# pc_heartypatch_v2_1.net
KiCad netlist of a schematic drawn in EAGLE
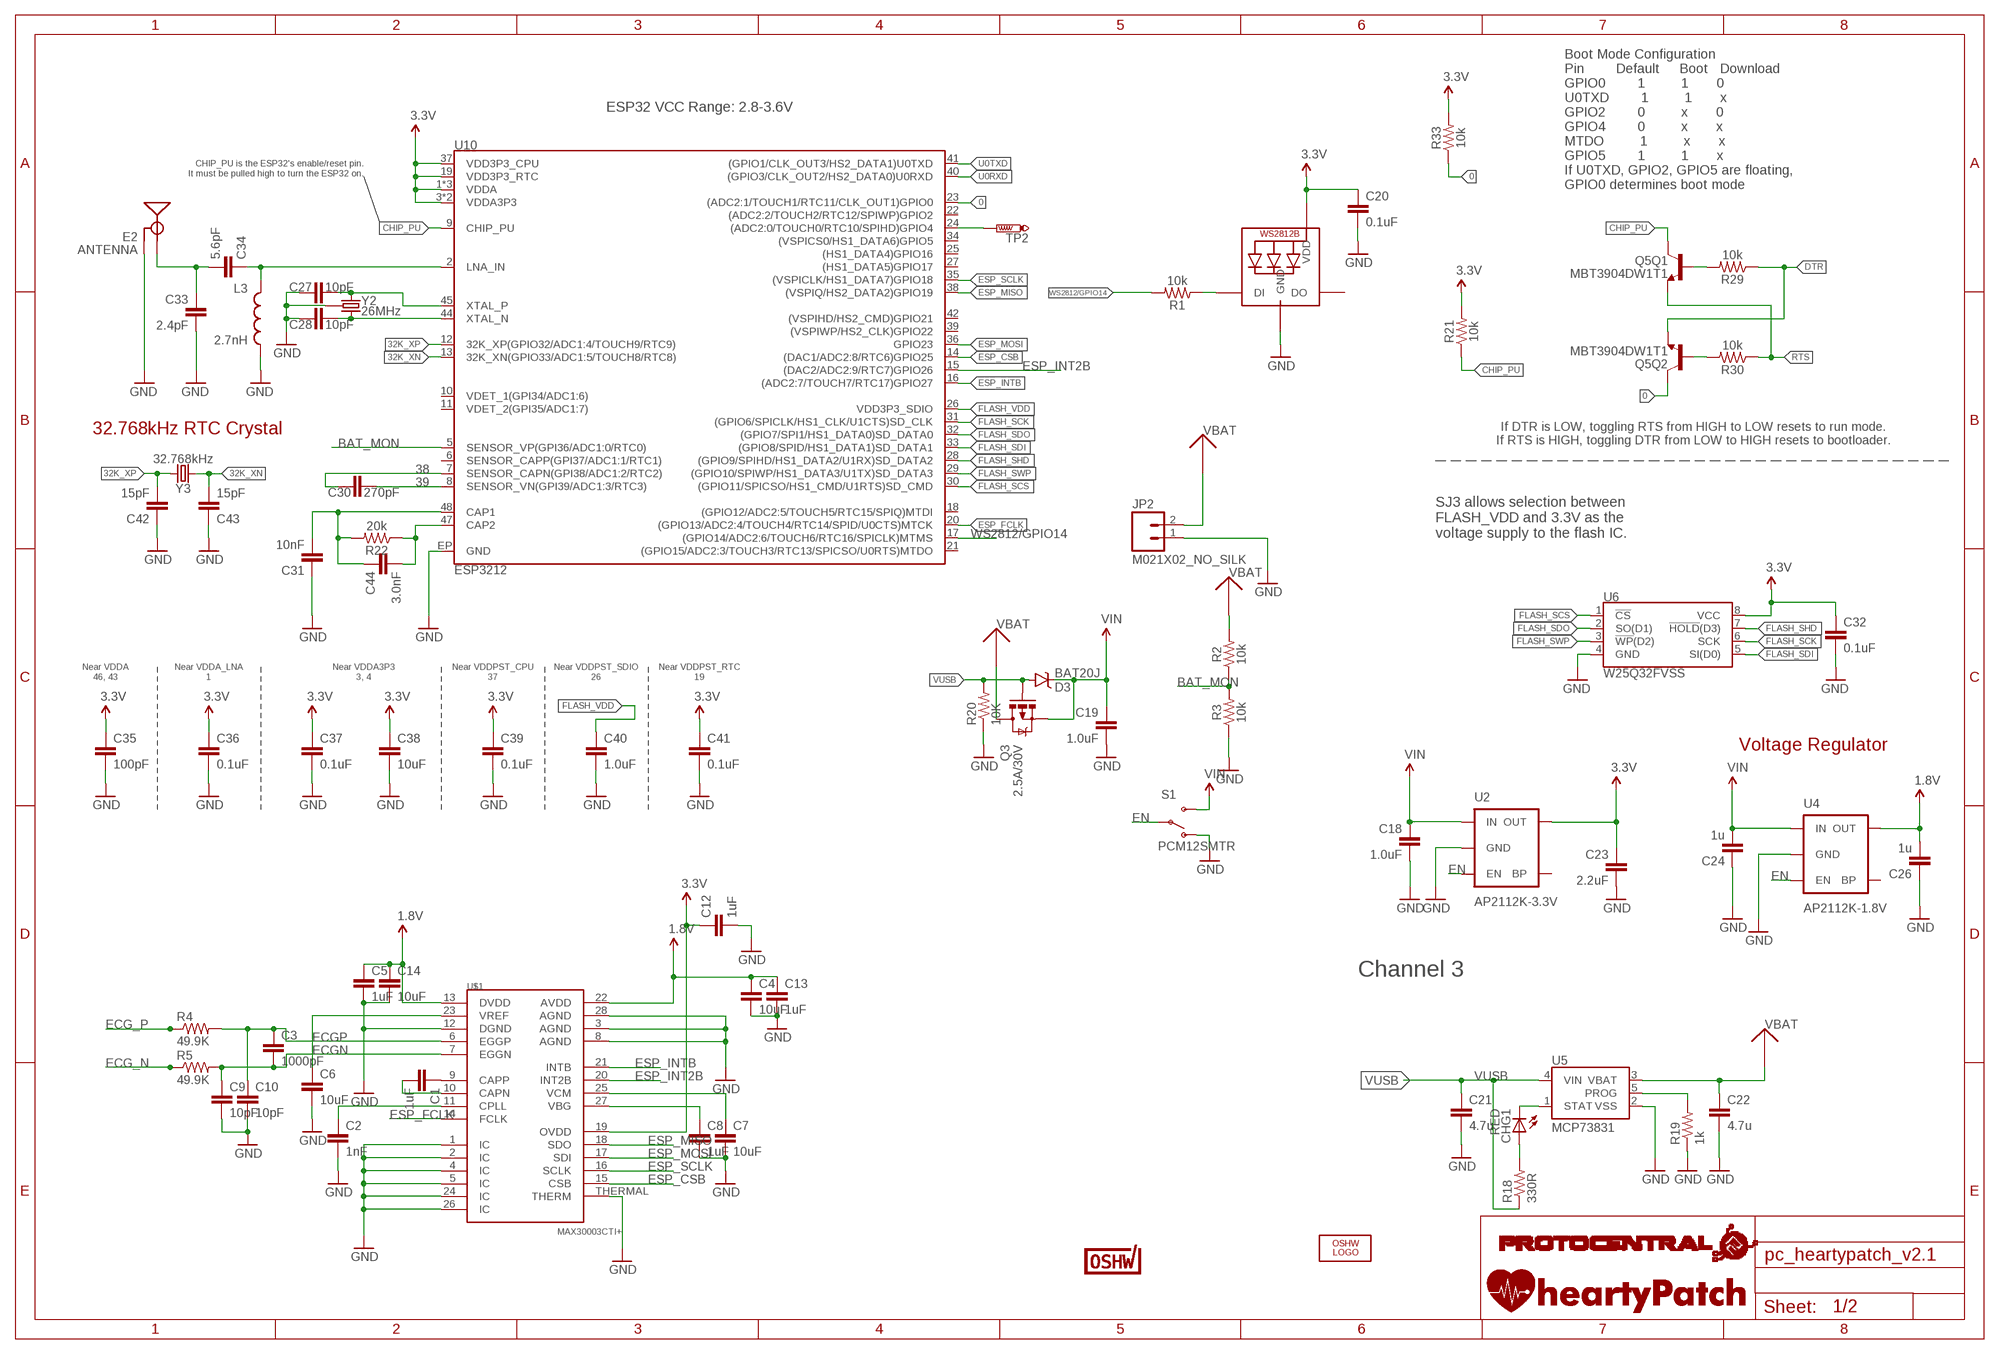
[diagram p0: schematic, sheet 1]
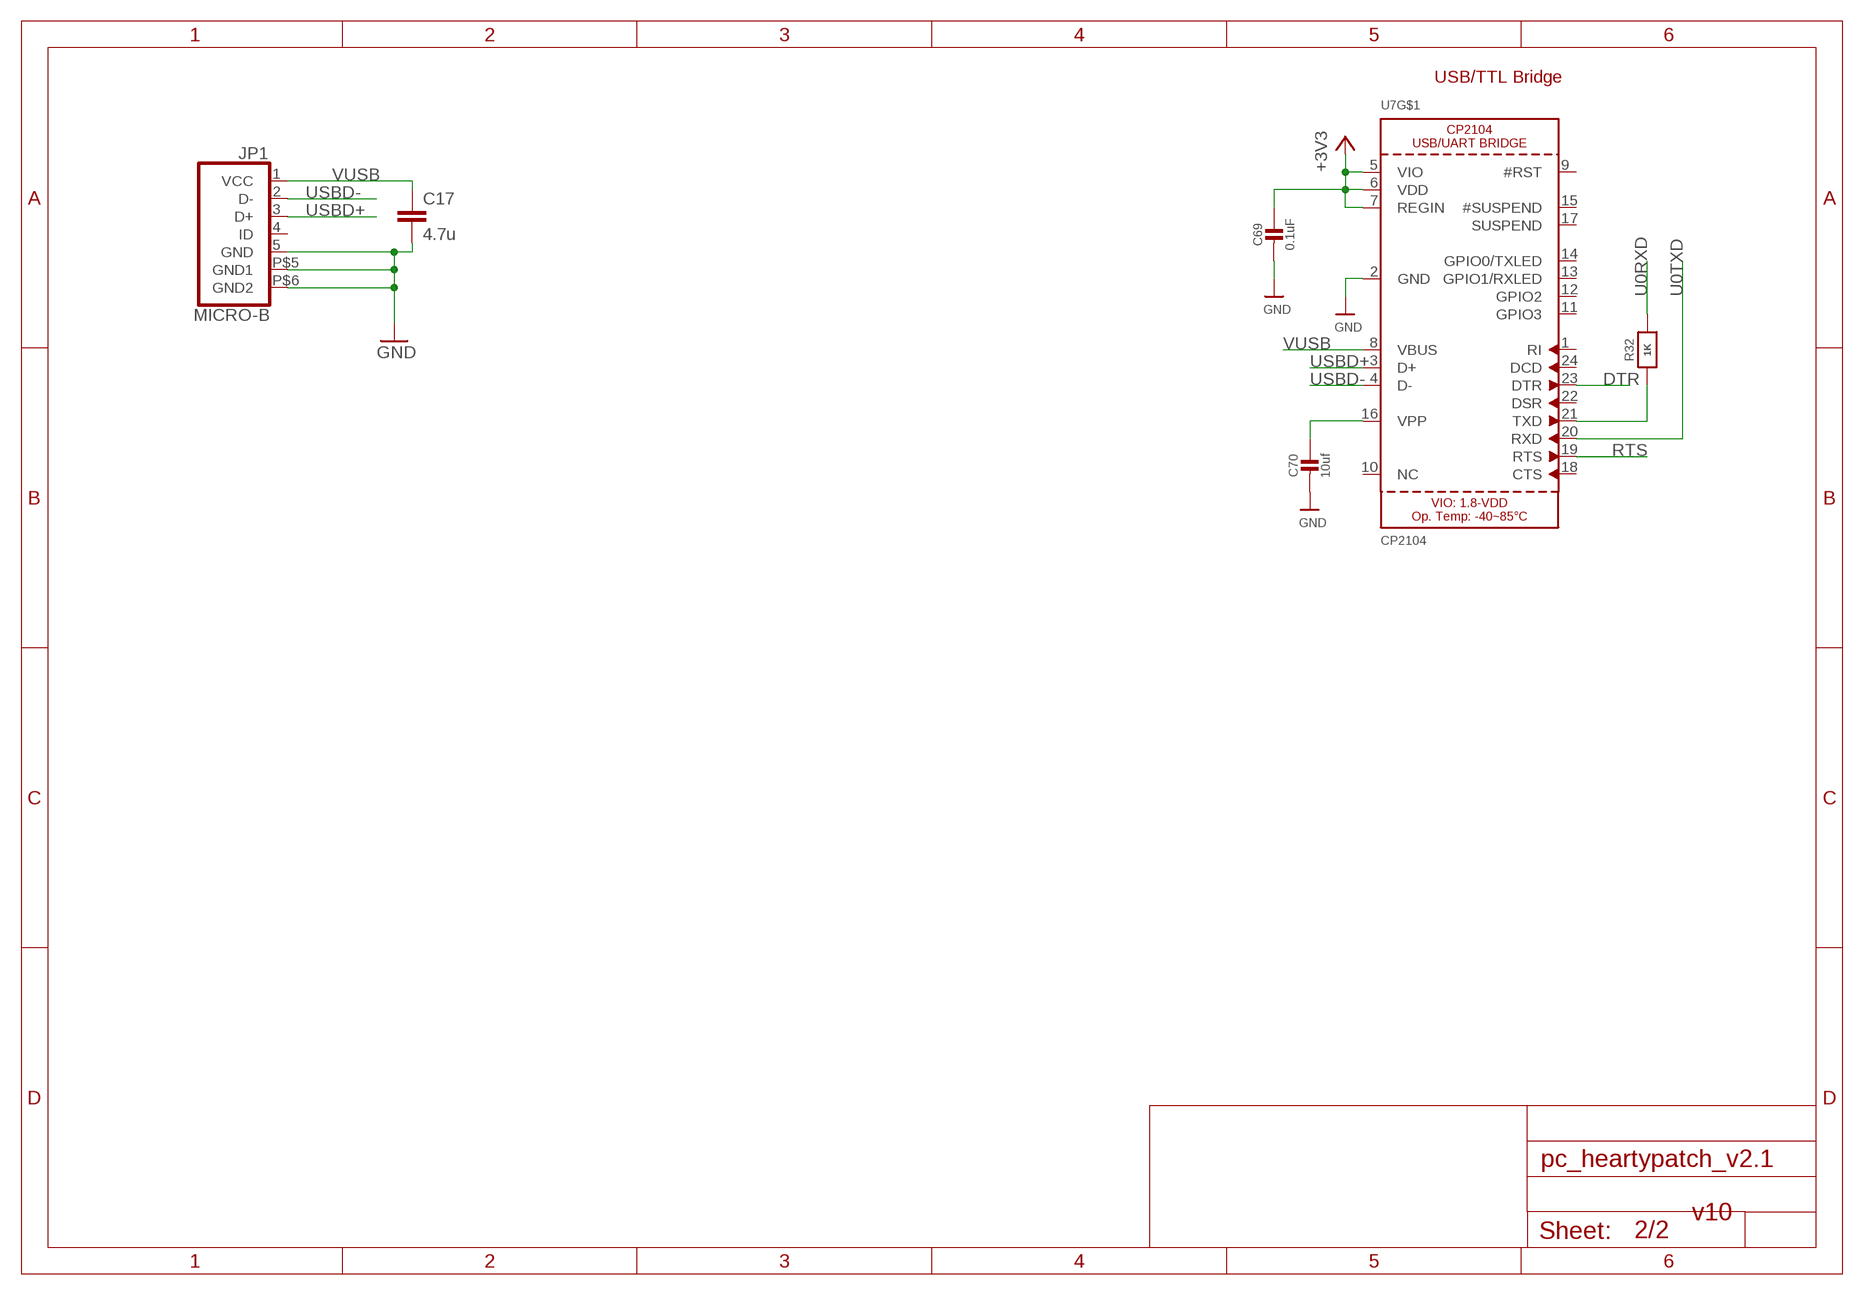
[diagram p1: schematic, sheet 2]

(export (version "E")
  (design (tool "Eeschema 10.0.6"))
  (components
    (comp (ref "C17")
      (value "4.7u")
      (footprint "eagle-import:C0805")
      (libsource (lib "eagle-import") (part "C-EUC0805"))
    )
    (comp (ref "C69")
      (value "0.1uF")
      (footprint "eagle-import:_0402")
      (libsource (lib "eagle-import") (part "CAP_CERAMIC_0402"))
    )
    (comp (ref "C70")
      (value "10uf")
      (footprint "eagle-import:0805-NO")
      (libsource (lib "eagle-import") (part "CAP_CERAMIC0805-NOOUTLINE"))
    )
    (comp (ref "JP1")
      (value "MICRO-B")
      (footprint "eagle-import:MICRO-B")
      (libsource (lib "eagle-import") (part "MICRO-B"))
    )
    (comp (ref "R32")
      (value "1K")
      (footprint "eagle-import:0603-NO")
      (libsource (lib "eagle-import") (part "RESISTOR_0603_NOOUT"))
    )
    (comp (ref "U7")
      (value "CP2104")
      (footprint "eagle-import:QFN24_4MM_SMSC")
      (libsource (lib "eagle-import") (part "CP2104"))
    )
    (comp (ref "C1")
      (value "1uF")
      (footprint "eagle-import:C0603")
      (libsource (lib "eagle-import") (part "C-EUC0603"))
    )
    (comp (ref "C2")
      (value "1nF")
      (footprint "eagle-import:C0603")
      (libsource (lib "eagle-import") (part "C-EUC0603"))
    )
    (comp (ref "C3")
      (value "1000pF")
      (footprint "eagle-import:C0402")
      (libsource (lib "eagle-import") (part "C-EUC0402"))
    )
    (comp (ref "C4")
      (value "10uF")
      (footprint "eagle-import:C0805")
      (libsource (lib "eagle-import") (part "C-EUC0805"))
    )
    (comp (ref "C5")
      (value "1uF")
      (footprint "eagle-import:C0402")
      (libsource (lib "eagle-import") (part "C-EUC0402"))
    )
    (comp (ref "C6")
      (value "10uF")
      (footprint "eagle-import:C0805")
      (libsource (lib "eagle-import") (part "C-EUC0805"))
    )
    (comp (ref "C7")
      (value "10uF")
      (footprint "eagle-import:C0805")
      (libsource (lib "eagle-import") (part "C-EUC0805"))
    )
    (comp (ref "C8")
      (value "1uF")
      (footprint "eagle-import:C0402")
      (libsource (lib "eagle-import") (part "C-EUC0402"))
    )
    (comp (ref "C9")
      (value "10pF")
      (footprint "eagle-import:C0402")
      (libsource (lib "eagle-import") (part "C-EUC0402"))
    )
    (comp (ref "C10")
      (value "10pF")
      (footprint "eagle-import:C0402")
      (libsource (lib "eagle-import") (part "C-EUC0402"))
    )
    (comp (ref "C12")
      (value "1uF")
      (footprint "eagle-import:C0402")
      (libsource (lib "eagle-import") (part "C-EUC0402"))
    )
    (comp (ref "C13")
      (value "1uF")
      (footprint "eagle-import:C0402")
      (libsource (lib "eagle-import") (part "C-EUC0402"))
    )
    (comp (ref "C14")
      (value "10uF")
      (footprint "eagle-import:C0603")
      (libsource (lib "eagle-import") (part "C-EUC0603"))
    )
    (comp (ref "C18")
      (value "1.0uF")
      (footprint "eagle-import:0805")
      (libsource (lib "eagle-import") (part "1.0UF-25V-+80/-20(0805)"))
    )
    (comp (ref "C19")
      (value "1.0uF")
      (footprint "eagle-import:C0402")
      (libsource (lib "eagle-import") (part "C-EUC0402"))
    )
    (comp (ref "C20")
      (value "0.1uF")
      (footprint "eagle-import:0603")
      (libsource (lib "eagle-import") (part "0.1UF-0603-25V-(+80/-20%)"))
    )
    (comp (ref "C21")
      (value "4.7u")
      (footprint "eagle-import:C0805")
      (libsource (lib "eagle-import") (part "C-EUC0805"))
    )
    (comp (ref "C22")
      (value "4.7u")
      (footprint "eagle-import:C0805")
      (libsource (lib "eagle-import") (part "C-EUC0805"))
    )
    (comp (ref "C23")
      (value "2.2uF")
      (footprint "eagle-import:C0805")
      (libsource (lib "eagle-import") (part "C-EUC0805"))
    )
    (comp (ref "C24")
      (value "1u")
      (footprint "eagle-import:C0805")
      (libsource (lib "eagle-import") (part "C-EUC0805"))
    )
    (comp (ref "C26")
      (value "1u")
      (footprint "eagle-import:C0805")
      (libsource (lib "eagle-import") (part "C-EUC0805"))
    )
    (comp (ref "C27")
      (value "10pF")
      (footprint "eagle-import:0603")
      (libsource (lib "eagle-import") (part "10PF-0603-50V-5%"))
    )
    (comp (ref "C28")
      (value "10pF")
      (footprint "eagle-import:0603")
      (libsource (lib "eagle-import") (part "10PF-0603-50V-5%"))
    )
    (comp (ref "C30")
      (value "270pF")
      (footprint "eagle-import:0603")
      (libsource (lib "eagle-import") (part "270PF-50V-5%(0603)"))
    )
    (comp (ref "C31")
      (value "10nF")
      (footprint "eagle-import:0603")
      (libsource (lib "eagle-import") (part "10NF-0603-50V-10%"))
    )
    (comp (ref "C32")
      (value "0.1uF")
      (footprint "eagle-import:0402")
      (libsource (lib "eagle-import") (part "0.1UF-0402-16V-10%"))
    )
    (comp (ref "C33")
      (value "2.4pF")
      (footprint "eagle-import:0603")
      (libsource (lib "eagle-import") (part "2.4PF-0603-50V-5%"))
    )
    (comp (ref "C34")
      (value "5.6pF")
      (footprint "eagle-import:0603")
      (libsource (lib "eagle-import") (part "5.6PF-50V-5%(0603)"))
    )
    (comp (ref "C35")
      (value "100pF")
      (footprint "eagle-import:0603")
      (libsource (lib "eagle-import") (part "100PF-0603-50V-5%"))
    )
    (comp (ref "C36")
      (value "0.1uF")
      (footprint "eagle-import:0603")
      (libsource (lib "eagle-import") (part "0.1UF-0603-25V-(+80/-20%)"))
    )
    (comp (ref "C37")
      (value "0.1uF")
      (footprint "eagle-import:0603")
      (libsource (lib "eagle-import") (part "0.1UF-0603-25V-(+80/-20%)"))
    )
    (comp (ref "C38")
      (value "10uF")
      (footprint "eagle-import:0603")
      (libsource (lib "eagle-import") (part "10UF-0603-6.3V-20%"))
    )
    (comp (ref "C39")
      (value "0.1uF")
      (footprint "eagle-import:0402")
      (libsource (lib "eagle-import") (part "0.1UF-0402-16V-10%"))
    )
    (comp (ref "C40")
      (value "1.0uF")
      (footprint "eagle-import:0603")
      (libsource (lib "eagle-import") (part "1.0UF-0603-16V-10%"))
    )
    (comp (ref "C41")
      (value "0.1uF")
      (footprint "eagle-import:0603")
      (libsource (lib "eagle-import") (part "0.1UF-0603-25V-(+80/-20%)"))
    )
    (comp (ref "C42")
      (value "15pF")
      (footprint "eagle-import:0603")
      (libsource (lib "eagle-import") (part "15PF-0603-50V-5%"))
    )
    (comp (ref "C43")
      (value "15pF")
      (footprint "eagle-import:0603")
      (libsource (lib "eagle-import") (part "15PF-0603-50V-5%"))
    )
    (comp (ref "C44")
      (value "3.0nF")
      (footprint "eagle-import:0603")
      (libsource (lib "eagle-import") (part "3.0NF-0603-50V-5%"))
    )
    (comp (ref "CHG1")
      (value "RED")
      (footprint "eagle-import:CHIPLED_0603")
      (libsource (lib "eagle-import") (part "LEDCHIPLED_0603"))
    )
    (comp (ref "D3")
      (value "BAT20J")
      (footprint "eagle-import:SOD-323")
      (libsource (lib "eagle-import") (part "DIODE-SCHOTTKY-BAT20J"))
    )
    (comp (ref "E2")
      (value "ANTENNA")
      (footprint "eagle-import:TRACE_ANTENNA_2.4GHZ_25.7MM_TUNED")
      (libsource (lib "eagle-import") (part "ANTENNATRACE-TUNED"))
    )
    (comp (ref "JP2")
      (value "M021X02_NO_SILK")
      (footprint "eagle-import:1X02_NO_SILK")
      (libsource (lib "eagle-import") (part "M021X02_NO_SILK"))
    )
    (comp (ref "L3")
      (value "2.7nH")
      (footprint "eagle-import:0603")
      (libsource (lib "eagle-import") (part "INDUCTOR0603"))
    )
    (comp (ref "LED1")
      (value "WS2812B5050")
      (footprint "eagle-import:WS2812B")
      (libsource (lib "eagle-import") (part "WS2812B5050"))
    )
    (comp (ref "LOGO1")
      (value "OSHW_LOGO_FILLX0200-NT")
      (footprint "eagle-import:OSHW_FILLX200_NOTEXT")
      (libsource (lib "eagle-import") (part "OSHW_LOGO_FILLX0200-NT"))
    )
    (comp (ref "Q3")
      (value "2.5A/30V")
      (footprint "eagle-import:SOT23-3")
      (libsource (lib "eagle-import") (part "MOSFET-PCHANNELDMG2307L"))
    )
    (comp (ref "Q5")
      (value "MBT3904DW1T1")
      (footprint "eagle-import:SC70-6")
      (libsource (lib "eagle-import") (part "MBT3904DW1T1"))
    )
    (comp (ref "R1")
      (value "10k")
      (footprint "eagle-import:0603")
      (libsource (lib "eagle-import") (part "10KOHM-1/10W-1%(0603)0603"))
    )
    (comp (ref "R2")
      (value "10k")
      (footprint "eagle-import:0603")
      (libsource (lib "eagle-import") (part "10KOHM-1/10W-1%(0603)0603"))
    )
    (comp (ref "R3")
      (value "10k")
      (footprint "eagle-import:0603")
      (libsource (lib "eagle-import") (part "10KOHM-1/10W-1%(0603)0603"))
    )
    (comp (ref "R4")
      (value "49.9K")
      (footprint "eagle-import:0805")
      (libsource (lib "eagle-import") (part "RESISTOR0805-RES"))
    )
    (comp (ref "R5")
      (value "49.9K")
      (footprint "eagle-import:0805")
      (libsource (lib "eagle-import") (part "RESISTOR0805-RES"))
    )
    (comp (ref "R18")
      (value "330R")
      (footprint "eagle-import:R0402")
      (libsource (lib "eagle-import") (part "R-US_R0402"))
    )
    (comp (ref "R19")
      (value "1k")
      (footprint "eagle-import:R0402")
      (libsource (lib "eagle-import") (part "R-US_R0402"))
    )
    (comp (ref "R20")
      (value "10K")
      (footprint "eagle-import:R0402")
      (libsource (lib "eagle-import") (part "R-US_R0402"))
    )
    (comp (ref "R21")
      (value "10k")
      (footprint "eagle-import:0603")
      (libsource (lib "eagle-import") (part "10KOHM-1/10W-1%(0603)0603"))
    )
    (comp (ref "R22")
      (value "20k")
      (footprint "eagle-import:0603")
      (libsource (lib "eagle-import") (part "20KOHM-0603-1/10W-1%"))
    )
    (comp (ref "R29")
      (value "10k")
      (footprint "eagle-import:0603")
      (libsource (lib "eagle-import") (part "10KOHM-0603-1/10W-1%"))
    )
    (comp (ref "R30")
      (value "10k")
      (footprint "eagle-import:0603")
      (libsource (lib "eagle-import") (part "10KOHM-0603-1/10W-1%"))
    )
    (comp (ref "R33")
      (value "10k")
      (footprint "eagle-import:0603")
      (libsource (lib "eagle-import") (part "10KOHM-1/10W-1%(0603)0603"))
    )
    (comp (ref "S1")
      (value "PCM12SMTR")
      (footprint "eagle-import:SWITCH-SPST-SMD-A")
      (libsource (lib "eagle-import") (part "SWITCH-SPDT-SMD-A"))
    )
    (comp (ref "TP2")
      (value "PTR1TP10SQ")
      (footprint "eagle-import:TP10SQ")
      (libsource (lib "eagle-import") (part "PTR1TP10SQ"))
    )
    (comp (ref "U$1")
      (value "MAX30003CTI+")
      (footprint "eagle-import:QFN-28")
      (libsource (lib "eagle-import") (part "MAX30003"))
    )
    (comp (ref "U$8")
      (value "HEARTYPATCHHEART")
      (footprint "eagle-import:HEARTYPATCH")
      (libsource (lib "eagle-import") (part "HEARTYPATCHHEART"))
    )
    (comp (ref "U$9")
      (value "PROTY_LOGO_WITH_TEXT")
      (footprint "eagle-import:PROTY_WITH_TEXT")
      (libsource (lib "eagle-import") (part "PROTY_LOGO_WITH_TEXT"))
    )
    (comp (ref "U$10")
      (value "CERT-SMALL")
      (footprint "eagle-import:CERT-SMALL-SILK")
      (libsource (lib "eagle-import") (part "CERT-SMALL"))
    )
    (comp (ref "U2")
      (value "AP2112K-3.3V")
      (footprint "eagle-import:SOT23-5")
      (libsource (lib "eagle-import") (part "V_REG_LDOSMD"))
    )
    (comp (ref "U4")
      (value "AP2112K-1.8V")
      (footprint "eagle-import:SOT23-5")
      (libsource (lib "eagle-import") (part "V_REG_LDOSMD"))
    )
    (comp (ref "U5")
      (value "MCP73831")
      (footprint "eagle-import:SOT23-5")
      (libsource (lib "eagle-import") (part "MCP73831"))
    )
    (comp (ref "U6")
      (value "W25Q32FVSS")
      (footprint "eagle-import:SOIC-8")
      (libsource (lib "eagle-import") (part "W25Q32FVSS"))
    )
    (comp (ref "U10")
      (value "ESP3212")
      (footprint "eagle-import:QFN48-0.4MM")
      (libsource (lib "eagle-import") (part "ESP3212"))
    )
    (comp (ref "Y2")
      (value "26MHz")
      (footprint "eagle-import:CRYSTAL-SMD-3.2X2.5")
      (libsource (lib "eagle-import") (part "CRYSTAL-GROUNDED3.2X2.5"))
    )
    (comp (ref "Y3")
      (value "32.768kHz")
      (footprint "eagle-import:CRYSTAL-SMD-3.2X1.5MM")
      (libsource (lib "eagle-import") (part "CRYSTAL-32.768KHZSMD-3.2X1.5"))
    )
  )
  (nets
    (net (code "1") (name "+3V3") (class "Default")
      (node (ref "C69") (pin "1") (pinfunction "1_1") (pintype "passive"))
      (node (ref "U7") (pin "5") (pinfunction "VIO_5") (pintype "power_in"))
      (node (ref "U7") (pin "6") (pinfunction "VDD_6") (pintype "power_in"))
      (node (ref "U7") (pin "7") (pinfunction "REGIN_7") (pintype "power_in"))
    )
    (net (code "2") (name "0") (class "Default")
      (node (ref "Q5") (pin "6") (pinfunction "C_6") (pintype "passive"))
      (node (ref "R33") (pin "1") (pinfunction "1_1") (pintype "passive"))
      (node (ref "U10") (pin "23") (pinfunction "(ADC2:1/TOUCH1/RTC11/CLK_OUT1)GPIO0_23") (pintype "bidirectional"))
    )
    (net (code "3") (name "1.8V") (class "Default")
      (node (ref "C13") (pin "1") (pinfunction "1_1") (pintype "passive"))
      (node (ref "C14") (pin "1") (pinfunction "1_1") (pintype "passive"))
      (node (ref "C26") (pin "2") (pinfunction "2_2") (pintype "passive"))
      (node (ref "C4") (pin "1") (pinfunction "1_1") (pintype "passive"))
      (node (ref "C5") (pin "1") (pinfunction "1_1") (pintype "passive"))
      (node (ref "U$1") (pin "13") (pinfunction "DVDD_13") (pintype "bidirectional"))
      (node (ref "U$1") (pin "22") (pinfunction "AVDD_22") (pintype "bidirectional"))
      (node (ref "U4") (pin "5") (pinfunction "OUT_5") (pintype "passive"))
    )
    (net (code "4") (name "3.3V") (class "Default")
      (node (ref "C12") (pin "1") (pinfunction "1_1") (pintype "passive"))
      (node (ref "C20") (pin "1") (pinfunction "1_1") (pintype "passive"))
      (node (ref "C23") (pin "1") (pinfunction "1_1") (pintype "passive"))
      (node (ref "C32") (pin "1") (pinfunction "1_1") (pintype "passive"))
      (node (ref "C35") (pin "1") (pinfunction "1_1") (pintype "passive"))
      (node (ref "C36") (pin "1") (pinfunction "1_1") (pintype "passive"))
      (node (ref "C37") (pin "1") (pinfunction "1_1") (pintype "passive"))
      (node (ref "C38") (pin "1") (pinfunction "1_1") (pintype "passive"))
      (node (ref "C39") (pin "1") (pinfunction "1_1") (pintype "passive"))
      (node (ref "C41") (pin "1") (pinfunction "1_1") (pintype "passive"))
      (node (ref "LED1") (pin "1-VDD") (pinfunction "VDD_1-VDD") (pintype "power_in"))
      (node (ref "R21") (pin "2") (pinfunction "2_2") (pintype "passive"))
      (node (ref "R33") (pin "2") (pinfunction "2_2") (pintype "passive"))
      (node (ref "U$1") (pin "19") (pinfunction "OVDD_19") (pintype "bidirectional"))
      (node (ref "U10") (pin "1") (pinfunction "VDDA_1") (pintype "bidirectional"))
      (node (ref "U10") (pin "19") (pinfunction "VDD3P3_RTC_19") (pintype "bidirectional"))
      (node (ref "U10") (pin "3") (pinfunction "VDDA3P3_3") (pintype "bidirectional"))
      (node (ref "U10") (pin "37") (pinfunction "VDD3P3_CPU_37") (pintype "bidirectional"))
      (node (ref "U10") (pin "4") (pinfunction "VDDA3P3_4") (pintype "bidirectional"))
      (node (ref "U10") (pin "43") (pinfunction "VDDA_43") (pintype "bidirectional"))
      (node (ref "U10") (pin "46") (pinfunction "VDDA_46") (pintype "bidirectional"))
      (node (ref "U2") (pin "5") (pinfunction "OUT_5") (pintype "passive"))
      (node (ref "U6") (pin "8") (pinfunction "VCC_8") (pintype "bidirectional"))
    )
    (net (code "5") (name "32K_XN") (class "Default")
      (node (ref "C43") (pin "2") (pinfunction "2_2") (pintype "passive"))
      (node (ref "U10") (pin "13") (pinfunction "32K_XN(GPIO33/ADC1:5/TOUCH8/RTC8)_13") (pintype "bidirectional"))
      (node (ref "Y3") (pin "P$2") (pinfunction "2_P$2") (pintype "passive"))
    )
    (net (code "6") (name "32K_XP") (class "Default")
      (node (ref "C42") (pin "2") (pinfunction "2_2") (pintype "passive"))
      (node (ref "U10") (pin "12") (pinfunction "32K_XP(GPIO32/ADC1:4/TOUCH9/RTC9)_12") (pintype "bidirectional"))
      (node (ref "Y3") (pin "P$1") (pinfunction "1_P$1") (pintype "passive"))
    )
    (net (code "7") (name "38") (class "Default")
      (node (ref "C30") (pin "1") (pinfunction "1_1") (pintype "passive"))
      (node (ref "U10") (pin "7") (pinfunction "SENSOR_CAPN(GPI38/ADC1:2/RTC2)_7") (pintype "bidirectional"))
    )
    (net (code "8") (name "39") (class "Default")
      (node (ref "C30") (pin "2") (pinfunction "2_2") (pintype "passive"))
      (node (ref "U10") (pin "8") (pinfunction "SENSOR_VN(GPI39/ADC1:3/RTC3)_8") (pintype "bidirectional"))
    )
    (net (code "9") (name "BAT_MON") (class "Default")
      (node (ref "R2") (pin "1") (pinfunction "1_1") (pintype "passive"))
      (node (ref "R3") (pin "2") (pinfunction "2_2") (pintype "passive"))
      (node (ref "U10") (pin "5") (pinfunction "SENSOR_VP(GPI36/ADC1:0/RTC0)_5") (pintype "bidirectional"))
    )
    (net (code "10") (name "CHIP_PU") (class "Default")
      (node (ref "Q5") (pin "3") (pinfunction "C_3") (pintype "passive"))
      (node (ref "R21") (pin "1") (pinfunction "1_1") (pintype "passive"))
      (node (ref "U10") (pin "9") (pinfunction "CHIP_PU_9") (pintype "bidirectional"))
    )
    (net (code "11") (name "DTR") (class "Default")
      (node (ref "Q5") (pin "1") (pinfunction "E_1") (pintype "passive"))
      (node (ref "R29") (pin "1") (pinfunction "1_1") (pintype "passive"))
      (node (ref "U7") (pin "23") (pinfunction "DTR_23") (pintype "output"))
    )
    (net (code "12") (name "ECGN") (class "Default")
      (node (ref "C3") (pin "2") (pinfunction "2_2") (pintype "passive"))
      (node (ref "C9") (pin "1") (pinfunction "1_1") (pintype "passive"))
      (node (ref "R5") (pin "2") (pinfunction "2_2") (pintype "passive"))
      (node (ref "U$1") (pin "7") (pinfunction "EGGN_7") (pintype "bidirectional"))
    )
    (net (code "13") (name "ECGP") (class "Default")
      (node (ref "C10") (pin "1") (pinfunction "1_1") (pintype "passive"))
      (node (ref "C3") (pin "1") (pinfunction "1_1") (pintype "passive"))
      (node (ref "R4") (pin "2") (pinfunction "2_2") (pintype "passive"))
      (node (ref "U$1") (pin "6") (pinfunction "EGGP_6") (pintype "bidirectional"))
    )
    (net (code "14") (name "ECG_N") (class "Default")
      (node (ref "R5") (pin "1") (pinfunction "1_1") (pintype "passive"))
    )
    (net (code "15") (name "ECG_P") (class "Default")
      (node (ref "R4") (pin "1") (pinfunction "1_1") (pintype "passive"))
    )
    (net (code "16") (name "EN") (class "Default")
      (node (ref "S1") (pin "2") (pinfunction "P_2") (pintype "passive"))
      (node (ref "U2") (pin "3") (pinfunction "EN_3") (pintype "input"))
      (node (ref "U4") (pin "3") (pinfunction "EN_3") (pintype "input"))
    )
    (net (code "17") (name "ESP_CSB") (class "Default")
      (node (ref "U$1") (pin "15") (pinfunction "CSB_15") (pintype "bidirectional"))
      (node (ref "U10") (pin "14") (pinfunction "(DAC1/ADC2:8/RTC6)GPIO25_14") (pintype "bidirectional"))
    )
    (net (code "18") (name "ESP_FCLK") (class "Default")
      (node (ref "U$1") (pin "14") (pinfunction "FCLK_14") (pintype "bidirectional"))
      (node (ref "U10") (pin "20") (pinfunction "(GPIO13/ADC2:4/TOUCH4/RTC14/SPID/U0CTS)MTCK_20") (pintype "bidirectional"))
    )
    (net (code "19") (name "ESP_INT2B") (class "Default")
      (node (ref "U$1") (pin "20") (pinfunction "INT2B_20") (pintype "bidirectional"))
      (node (ref "U10") (pin "15") (pinfunction "(DAC2/ADC2:9/RTC7)GPIO26_15") (pintype "bidirectional"))
    )
    (net (code "20") (name "ESP_INTB") (class "Default")
      (node (ref "U$1") (pin "21") (pinfunction "INTB_21") (pintype "bidirectional"))
      (node (ref "U10") (pin "16") (pinfunction "(ADC2:7/TOUCH7/RTC17)GPIO27_16") (pintype "bidirectional"))
    )
    (net (code "21") (name "ESP_MISO") (class "Default")
      (node (ref "U$1") (pin "18") (pinfunction "SDO_18") (pintype "bidirectional"))
      (node (ref "U10") (pin "38") (pinfunction "(VSPIQ/HS2_DATA2)GPIO19_38") (pintype "bidirectional"))
    )
    (net (code "22") (name "ESP_MOSI") (class "Default")
      (node (ref "U$1") (pin "17") (pinfunction "SDI_17") (pintype "bidirectional"))
      (node (ref "U10") (pin "36") (pinfunction "GPIO23_36") (pintype "bidirectional"))
    )
    (net (code "23") (name "ESP_SCLK") (class "Default")
      (node (ref "U$1") (pin "16") (pinfunction "SCLK_16") (pintype "bidirectional"))
      (node (ref "U10") (pin "35") (pinfunction "(VSPICLK/HS1_DATA7)GPIO18_35") (pintype "bidirectional"))
    )
    (net (code "24") (name "FLASH_SCK") (class "Default")
      (node (ref "U10") (pin "31") (pinfunction "(GPIO6/SPICLK/HS1_CLK/U1CTS)SD_CLK_31") (pintype "bidirectional"))
      (node (ref "U6") (pin "6") (pinfunction "SCK_6") (pintype "bidirectional"))
    )
    (net (code "25") (name "FLASH_SCS") (class "Default")
      (node (ref "U10") (pin "30") (pinfunction "(GPIO11/SPICSO/HS1_CMD/U1RTS)SD_CMD_30") (pintype "bidirectional"))
      (node (ref "U6") (pin "1") (pinfunction "~{CS}_1") (pintype "bidirectional"))
    )
    (net (code "26") (name "FLASH_SDI") (class "Default")
      (node (ref "U10") (pin "33") (pinfunction "(GPIO8/SPID/HS1_DATA1)SD_DATA1_33") (pintype "bidirectional"))
      (node (ref "U6") (pin "5") (pinfunction "SI(D0)_5") (pintype "bidirectional"))
    )
    (net (code "27") (name "FLASH_SDO") (class "Default")
      (node (ref "U10") (pin "32") (pinfunction "(GPIO7/SPI1/HS1_DATA0)SD_DATA0_32") (pintype "bidirectional"))
      (node (ref "U6") (pin "2") (pinfunction "SO(D1)_2") (pintype "bidirectional"))
    )
    (net (code "28") (name "FLASH_SHD") (class "Default")
      (node (ref "U10") (pin "28") (pinfunction "(GPIO9/SPIHD/HS1_DATA2/U1RX)SD_DATA2_28") (pintype "bidirectional"))
      (node (ref "U6") (pin "7") (pinfunction "~{HOLD}(D3)_7") (pintype "bidirectional"))
    )
    (net (code "29") (name "FLASH_SWP") (class "Default")
      (node (ref "U10") (pin "29") (pinfunction "(GPIO10/SPIWP/HS1_DATA3/U1TX)SD_DATA3_29") (pintype "bidirectional"))
      (node (ref "U6") (pin "3") (pinfunction "~{WP}(D2)_3") (pintype "bidirectional"))
    )
    (net (code "30") (name "FLASH_VDD") (class "Default")
      (node (ref "C40") (pin "1") (pinfunction "1_1") (pintype "passive"))
      (node (ref "U10") (pin "26") (pinfunction "VDD3P3_SDIO_26") (pintype "bidirectional"))
    )
    (net (code "31") (name "GND") (class "Default")
      (node (ref "C10") (pin "2") (pinfunction "2_2") (pintype "passive"))
      (node (ref "C12") (pin "2") (pinfunction "2_2") (pintype "passive"))
      (node (ref "C13") (pin "2") (pinfunction "2_2") (pintype "passive"))
      (node (ref "C14") (pin "2") (pinfunction "2_2") (pintype "passive"))
      (node (ref "C17") (pin "2") (pinfunction "2_2") (pintype "passive"))
      (node (ref "C18") (pin "2") (pinfunction "2_2") (pintype "passive"))
      (node (ref "C19") (pin "2") (pinfunction "2_2") (pintype "passive"))
      (node (ref "C2") (pin "2") (pinfunction "2_2") (pintype "passive"))
      (node (ref "C20") (pin "2") (pinfunction "2_2") (pintype "passive"))
      (node (ref "C21") (pin "2") (pinfunction "2_2") (pintype "passive"))
      (node (ref "C22") (pin "2") (pinfunction "2_2") (pintype "passive"))
      (node (ref "C23") (pin "2") (pinfunction "2_2") (pintype "passive"))
      (node (ref "C24") (pin "1") (pinfunction "1_1") (pintype "passive"))
      (node (ref "C26") (pin "1") (pinfunction "1_1") (pintype "passive"))
      (node (ref "C27") (pin "1") (pinfunction "1_1") (pintype "passive"))
      (node (ref "C28") (pin "1") (pinfunction "1_1") (pintype "passive"))
      (node (ref "C31") (pin "1") (pinfunction "1_1") (pintype "passive"))
      (node (ref "C32") (pin "2") (pinfunction "2_2") (pintype "passive"))
      (node (ref "C33") (pin "2") (pinfunction "2_2") (pintype "passive"))
      (node (ref "C35") (pin "2") (pinfunction "2_2") (pintype "passive"))
      (node (ref "C36") (pin "2") (pinfunction "2_2") (pintype "passive"))
      (node (ref "C37") (pin "2") (pinfunction "2_2") (pintype "passive"))
      (node (ref "C38") (pin "2") (pinfunction "2_2") (pintype "passive"))
      (node (ref "C39") (pin "2") (pinfunction "2_2") (pintype "passive"))
      (node (ref "C4") (pin "2") (pinfunction "2_2") (pintype "passive"))
      (node (ref "C40") (pin "2") (pinfunction "2_2") (pintype "passive"))
      (node (ref "C41") (pin "2") (pinfunction "2_2") (pintype "passive"))
      (node (ref "C42") (pin "1") (pinfunction "1_1") (pintype "passive"))
      (node (ref "C43") (pin "1") (pinfunction "1_1") (pintype "passive"))
      (node (ref "C5") (pin "2") (pinfunction "2_2") (pintype "passive"))
      (node (ref "C6") (pin "2") (pinfunction "2_2") (pintype "passive"))
      (node (ref "C69") (pin "2") (pinfunction "2_2") (pintype "passive"))
      (node (ref "C7") (pin "2") (pinfunction "2_2") (pintype "passive"))
      (node (ref "C70") (pin "2") (pinfunction "2_2") (pintype "passive"))
      (node (ref "C8") (pin "2") (pinfunction "2_2") (pintype "passive"))
      (node (ref "C9") (pin "2") (pinfunction "2_2") (pintype "passive"))
      (node (ref "E2") (pin "GND") (pinfunction "GND_GND") (pintype "bidirectional"))
      (node (ref "E2") (pin "GND2") (pinfunction "GND_GND2") (pintype "bidirectional"))
      (node (ref "JP1") (pin "5") (pinfunction "GND_5") (pintype "bidirectional"))
      (node (ref "JP1") (pin "P$5") (pinfunction "GND1_P$5") (pintype "bidirectional"))
      (node (ref "JP1") (pin "P$6") (pinfunction "GND2_P$6") (pintype "bidirectional"))
      (node (ref "JP2") (pin "1") (pinfunction "1_1") (pintype "passive"))
      (node (ref "L3") (pin "2") (pinfunction "2_2") (pintype "passive"))
      (node (ref "LED1") (pin "3-GND") (pinfunction "GND_3-GND") (pintype "power_in"))
      (node (ref "R19") (pin "1") (pinfunction "1_1") (pintype "passive"))
      (node (ref "R20") (pin "1") (pinfunction "1_1") (pintype "passive"))
      (node (ref "R3") (pin "1") (pinfunction "1_1") (pintype "passive"))
      (node (ref "S1") (pin "1") (pinfunction "O_1") (pintype "passive"))
      (node (ref "U$1") (pin "1") (pinfunction "IC_1") (pintype "bidirectional"))
      (node (ref "U$1") (pin "12") (pinfunction "DGND_12") (pintype "bidirectional"))
      (node (ref "U$1") (pin "2") (pinfunction "IC_2") (pintype "bidirectional"))
      (node (ref "U$1") (pin "24") (pinfunction "IC_24") (pintype "bidirectional"))
      (node (ref "U$1") (pin "26") (pinfunction "IC_26") (pintype "bidirectional"))
      (node (ref "U$1") (pin "28") (pinfunction "AGND_28") (pintype "bidirectional"))
      (node (ref "U$1") (pin "3") (pinfunction "AGND_3") (pintype "bidirectional"))
      (node (ref "U$1") (pin "4") (pinfunction "IC_4") (pintype "bidirectional"))
      (node (ref "U$1") (pin "5") (pinfunction "IC_5") (pintype "bidirectional"))
      (node (ref "U$1") (pin "8") (pinfunction "AGND_8") (pintype "bidirectional"))
      (node (ref "U$1") (pin "THERMAL") (pinfunction "THERM_THERMAL") (pintype "bidirectional"))
      (node (ref "U10") (pin "EP") (pinfunction "GND_EP") (pintype "bidirectional"))
      (node (ref "U2") (pin "2") (pinfunction "GND_2") (pintype "input"))
      (node (ref "U4") (pin "2") (pinfunction "GND_2") (pintype "input"))
      (node (ref "U5") (pin "2") (pinfunction "VSS_2") (pintype "power_in"))
      (node (ref "U6") (pin "4") (pinfunction "GND_4") (pintype "bidirectional"))
      (node (ref "U7") (pin "2") (pinfunction "GND_2") (pintype "power_in"))
      (node (ref "Y2") (pin "2") (pinfunction "GND_2") (pintype "passive"))
      (node (ref "Y2") (pin "4") (pinfunction "GND_4") (pintype "passive"))
    )
    (net (code "32") (name "Net-(CHG1-PadA)") (class "Default")
      (node (ref "CHG1") (pin "A") (pinfunction "A_A") (pintype "passive"))
      (node (ref "R18") (pin "2") (pinfunction "2_2") (pintype "passive"))
    )
    (net (code "33") (name "Net-(E2-SIGNAL)") (class "Default")
      (node (ref "C33") (pin "1") (pinfunction "1_1") (pintype "passive"))
      (node (ref "C34") (pin "2") (pinfunction "2_2") (pintype "passive"))
      (node (ref "E2") (pin "ANT") (pinfunction "SIGNAL_ANT") (pintype "bidirectional"))
    )
    (net (code "34") (name "Net-(LED1-DI)") (class "Default")
      (node (ref "LED1") (pin "4-DIN") (pinfunction "DI_4-DIN") (pintype "input"))
      (node (ref "R1") (pin "1") (pinfunction "1_1") (pintype "passive"))
    )
    (net (code "35") (name "Net-(Q5A-B)") (class "Default")
      (node (ref "Q5") (pin "5") (pinfunction "B_5") (pintype "passive"))
      (node (ref "R29") (pin "2") (pinfunction "2_2") (pintype "passive"))
    )
    (net (code "36") (name "Net-(Q5B-B)") (class "Default")
      (node (ref "Q5") (pin "2") (pinfunction "B_2") (pintype "passive"))
      (node (ref "R30") (pin "2") (pinfunction "2_2") (pintype "passive"))
    )
    (net (code "37") (name "Net-(U$1-CAPN)") (class "Default")
      (node (ref "C1") (pin "2") (pinfunction "2_2") (pintype "passive"))
      (node (ref "U$1") (pin "10") (pinfunction "CAPN_10") (pintype "bidirectional"))
    )
    (net (code "38") (name "Net-(U$1-CAPP)") (class "Default")
      (node (ref "C1") (pin "1") (pinfunction "1_1") (pintype "passive"))
      (node (ref "U$1") (pin "9") (pinfunction "CAPP_9") (pintype "bidirectional"))
    )
    (net (code "39") (name "Net-(U$1-CPLL)") (class "Default")
      (node (ref "C2") (pin "1") (pinfunction "1_1") (pintype "passive"))
      (node (ref "U$1") (pin "11") (pinfunction "CPLL_11") (pintype "bidirectional"))
    )
    (net (code "40") (name "Net-(U$1-VBG)") (class "Default")
      (node (ref "C8") (pin "1") (pinfunction "1_1") (pintype "passive"))
      (node (ref "U$1") (pin "27") (pinfunction "VBG_27") (pintype "bidirectional"))
    )
    (net (code "41") (name "Net-(U$1-VCM)") (class "Default")
      (node (ref "C7") (pin "1") (pinfunction "1_1") (pintype "passive"))
      (node (ref "U$1") (pin "25") (pinfunction "VCM_25") (pintype "bidirectional"))
    )
    (net (code "42") (name "Net-(U$1-VREF)") (class "Default")
      (node (ref "C6") (pin "1") (pinfunction "1_1") (pintype "passive"))
      (node (ref "U$1") (pin "23") (pinfunction "VREF_23") (pintype "bidirectional"))
    )
    (net (code "43") (name "Net-(U5-PROG)") (class "Default")
      (node (ref "R19") (pin "2") (pinfunction "2_2") (pintype "passive"))
      (node (ref "U5") (pin "5") (pinfunction "PROG_5") (pintype "input"))
    )
    (net (code "44") (name "Net-(U5-STAT)") (class "Default")
      (node (ref "CHG1") (pin "C") (pinfunction "C_C") (pintype "passive"))
      (node (ref "U5") (pin "1") (pinfunction "STAT_1") (pintype "output"))
    )
    (net (code "45") (name "Net-(U7A-TXD)") (class "Default")
      (node (ref "R32") (pin "1") (pinfunction "1_1") (pintype "passive"))
      (node (ref "U7") (pin "21") (pinfunction "TXD_21") (pintype "output"))
    )
    (net (code "46") (name "Net-(U7A-VPP)") (class "Default")
      (node (ref "C70") (pin "1") (pinfunction "1_1") (pintype "passive"))
      (node (ref "U7") (pin "16") (pinfunction "VPP_16") (pintype "bidirectional"))
    )
    (net (code "47") (name "Net-(U10-(ADC2:0{slash}TOUCH0{slash}RTC10{slash}SPIHD)GPIO4)") (class "Default")
      (node (ref "TP2") (pin "TP") (pinfunction "TP_TP") (pintype "input"))
      (node (ref "U10") (pin "24") (pinfunction "(ADC2:0/TOUCH0/RTC10/SPIHD)GPIO4_24") (pintype "bidirectional"))
    )
    (net (code "48") (name "Net-(U10-CAP1)") (class "Default")
      (node (ref "C31") (pin "2") (pinfunction "2_2") (pintype "passive"))
      (node (ref "C44") (pin "1") (pinfunction "1_1") (pintype "passive"))
      (node (ref "R22") (pin "2") (pinfunction "2_2") (pintype "passive"))
      (node (ref "U10") (pin "48") (pinfunction "CAP1_48") (pintype "bidirectional"))
    )
    (net (code "49") (name "Net-(U10-CAP2)") (class "Default")
      (node (ref "C44") (pin "2") (pinfunction "2_2") (pintype "passive"))
      (node (ref "R22") (pin "1") (pinfunction "1_1") (pintype "passive"))
      (node (ref "U10") (pin "47") (pinfunction "CAP2_47") (pintype "bidirectional"))
    )
    (net (code "50") (name "Net-(U10-LNA_IN)") (class "Default")
      (node (ref "C34") (pin "1") (pinfunction "1_1") (pintype "passive"))
      (node (ref "L3") (pin "1") (pinfunction "1_1") (pintype "passive"))
      (node (ref "U10") (pin "2") (pinfunction "LNA_IN_2") (pintype "bidirectional"))
    )
    (net (code "51") (name "Net-(U10-XTAL_N)") (class "Default")
      (node (ref "C28") (pin "2") (pinfunction "2_2") (pintype "passive"))
      (node (ref "U10") (pin "44") (pinfunction "XTAL_N_44") (pintype "bidirectional"))
      (node (ref "Y2") (pin "3") (pinfunction "2_3") (pintype "passive"))
    )
    (net (code "52") (name "Net-(U10-XTAL_P)") (class "Default")
      (node (ref "C27") (pin "2") (pinfunction "2_2") (pintype "passive"))
      (node (ref "U10") (pin "45") (pinfunction "XTAL_P_45") (pintype "bidirectional"))
      (node (ref "Y2") (pin "1") (pinfunction "1_1") (pintype "passive"))
    )
    (net (code "53") (name "RTS") (class "Default")
      (node (ref "Q5") (pin "4") (pinfunction "E_4") (pintype "passive"))
      (node (ref "R30") (pin "1") (pinfunction "1_1") (pintype "passive"))
      (node (ref "U7") (pin "19") (pinfunction "RTS_19") (pintype "output"))
    )
    (net (code "54") (name "U0RXD") (class "Default")
      (node (ref "R32") (pin "2") (pinfunction "2_2") (pintype "passive"))
      (node (ref "U10") (pin "40") (pinfunction "(GPIO3/CLK_OUT2/HS2_DATA0)U0RXD_40") (pintype "bidirectional"))
    )
    (net (code "55") (name "U0TXD") (class "Default")
      (node (ref "U10") (pin "41") (pinfunction "(GPIO1/CLK_OUT3/HS2_DATA1)U0TXD_41") (pintype "bidirectional"))
      (node (ref "U7") (pin "20") (pinfunction "RXD_20") (pintype "input"))
    )
    (net (code "56") (name "USBD+") (class "Default")
      (node (ref "JP1") (pin "3") (pinfunction "D+_3") (pintype "bidirectional"))
      (node (ref "U7") (pin "3") (pinfunction "D+_3") (pintype "bidirectional"))
    )
    (net (code "57") (name "USBD-") (class "Default")
      (node (ref "JP1") (pin "2") (pinfunction "D-_2") (pintype "bidirectional"))
      (node (ref "U7") (pin "4") (pinfunction "D-_4") (pintype "bidirectional"))
    )
    (net (code "58") (name "VBAT") (class "Default")
      (node (ref "C22") (pin "1") (pinfunction "1_1") (pintype "passive"))
      (node (ref "JP2") (pin "2") (pinfunction "2_2") (pintype "passive"))
      (node (ref "Q3") (pin "3") (pinfunction "D_3") (pintype "passive"))
      (node (ref "R2") (pin "2") (pinfunction "2_2") (pintype "passive"))
      (node (ref "U5") (pin "3") (pinfunction "VBAT_3") (pintype "power_in"))
    )
    (net (code "59") (name "VIN") (class "Default")
      (node (ref "C18") (pin "1") (pinfunction "1_1") (pintype "passive"))
      (node (ref "C19") (pin "1") (pinfunction "1_1") (pintype "passive"))
      (node (ref "C24") (pin "2") (pinfunction "2_2") (pintype "passive"))
      (node (ref "D3") (pin "C") (pinfunction "C_C") (pintype "passive"))
      (node (ref "Q3") (pin "2") (pinfunction "S_2") (pintype "passive"))
      (node (ref "S1") (pin "3") (pinfunction "S_3") (pintype "passive"))
      (node (ref "U2") (pin "1") (pinfunction "IN_1") (pintype "input"))
      (node (ref "U4") (pin "1") (pinfunction "IN_1") (pintype "input"))
    )
    (net (code "60") (name "VUSB") (class "Default")
      (node (ref "C17") (pin "1") (pinfunction "1_1") (pintype "passive"))
      (node (ref "C21") (pin "1") (pinfunction "1_1") (pintype "passive"))
      (node (ref "D3") (pin "A") (pinfunction "A_A") (pintype "passive"))
      (node (ref "JP1") (pin "1") (pinfunction "VCC_1") (pintype "bidirectional"))
      (node (ref "Q3") (pin "1") (pinfunction "G_1") (pintype "passive"))
      (node (ref "R18") (pin "1") (pinfunction "1_1") (pintype "passive"))
      (node (ref "R20") (pin "2") (pinfunction "2_2") (pintype "passive"))
      (node (ref "U5") (pin "4") (pinfunction "VIN_4") (pintype "power_in"))
      (node (ref "U7") (pin "8") (pinfunction "VBUS_8") (pintype "power_in"))
    )
    (net (code "61") (name "WS2812{slash}GPIO14") (class "Default")
      (node (ref "R1") (pin "2") (pinfunction "2_2") (pintype "passive"))
      (node (ref "U10") (pin "17") (pinfunction "(GPIO14/ADC2:6/TOUCH6/RTC16/SPICLK)MTMS_17") (pintype "bidirectional"))
    )
    (net (code "62") (name "unconnected-(JP1-ID-Pad4)") (class "Default")
      (node (ref "JP1") (pin "4") (pinfunction "ID_4") (pintype "bidirectional"))
    )
    (net (code "63") (name "unconnected-(LED1-DO-Pad2-DOUT)") (class "Default")
      (node (ref "LED1") (pin "2-DOUT") (pinfunction "DO_2-DOUT") (pintype "output"))
    )
    (net (code "64") (name "unconnected-(U2-BP-Pad4)") (class "Default")
      (node (ref "U2") (pin "4") (pinfunction "BP_4") (pintype "input"))
    )
    (net (code "65") (name "unconnected-(U4-BP-Pad4)") (class "Default")
      (node (ref "U4") (pin "4") (pinfunction "BP_4") (pintype "input"))
    )
    (net (code "66") (name "unconnected-(U7A-#RST-Pad9)") (class "Default")
      (node (ref "U7") (pin "9") (pinfunction "#RST_9") (pintype "bidirectional"))
    )
    (net (code "67") (name "unconnected-(U7A-#SUSPEND-Pad15)") (class "Default")
      (node (ref "U7") (pin "15") (pinfunction "#SUSPEND_15") (pintype "output"))
    )
    (net (code "68") (name "unconnected-(U7A-CTS-Pad18)") (class "Default")
      (node (ref "U7") (pin "18") (pinfunction "CTS_18") (pintype "input"))
    )
    (net (code "69") (name "unconnected-(U7A-DCD-Pad24)") (class "Default")
      (node (ref "U7") (pin "24") (pinfunction "DCD_24") (pintype "input"))
    )
    (net (code "70") (name "unconnected-(U7A-DSR-Pad22)") (class "Default")
      (node (ref "U7") (pin "22") (pinfunction "DSR_22") (pintype "input"))
    )
    (net (code "71") (name "unconnected-(U7A-GPIO0{slash}TXLED-Pad14)") (class "Default")
      (node (ref "U7") (pin "14") (pinfunction "GPIO0/TXLED_14") (pintype "bidirectional"))
    )
    (net (code "72") (name "unconnected-(U7A-GPIO1{slash}RXLED-Pad13)") (class "Default")
      (node (ref "U7") (pin "13") (pinfunction "GPIO1/RXLED_13") (pintype "bidirectional"))
    )
    (net (code "73") (name "unconnected-(U7A-GPIO2-Pad12)") (class "Default")
      (node (ref "U7") (pin "12") (pinfunction "GPIO2_12") (pintype "bidirectional"))
    )
    (net (code "74") (name "unconnected-(U7A-GPIO3-Pad11)") (class "Default")
      (node (ref "U7") (pin "11") (pinfunction "GPIO3_11") (pintype "bidirectional"))
    )
    (net (code "75") (name "unconnected-(U7A-NC-Pad10)") (class "Default")
      (node (ref "U7") (pin "10") (pinfunction "NC_10") (pintype "no_connect"))
    )
    (net (code "76") (name "unconnected-(U7A-RI-Pad1)") (class "Default")
      (node (ref "U7") (pin "1") (pinfunction "RI_1") (pintype "input"))
    )
    (net (code "77") (name "unconnected-(U7A-SUSPEND-Pad17)") (class "Default")
      (node (ref "U7") (pin "17") (pinfunction "SUSPEND_17") (pintype "output"))
    )
    (net (code "78") (name "unconnected-(U10-(ADC2:2{slash}TOUCH2{slash}RTC12{slash}SPIWP)GPIO2-Pad22)") (class "Default")
      (node (ref "U10") (pin "22") (pinfunction "(ADC2:2/TOUCH2/RTC12/SPIWP)GPIO2_22") (pintype "bidirectional"))
    )
    (net (code "79") (name "unconnected-(U10-(GPIO12{slash}ADC2:5{slash}TOUCH5{slash}RTC15{slash}SPIQ)MTDI-Pad18)") (class "Default")
      (node (ref "U10") (pin "18") (pinfunction "(GPIO12/ADC2:5/TOUCH5/RTC15/SPIQ)MTDI_18") (pintype "bidirectional"))
    )
    (net (code "80") (name "unconnected-(U10-(GPIO15{slash}ADC2:3{slash}TOUCH3{slash}RTC13{slash}SPICSO{slash}U0RTS)MTDO-Pad21)") (class "Default")
      (node (ref "U10") (pin "21") (pinfunction "(GPIO15/ADC2:3/TOUCH3/RTC13/SPICSO/U0RTS)MTDO_21") (pintype "bidirectional"))
    )
    (net (code "81") (name "unconnected-(U10-(HS1_DATA4)GPIO16-Pad25)") (class "Default")
      (node (ref "U10") (pin "25") (pinfunction "(HS1_DATA4)GPIO16_25") (pintype "bidirectional"))
    )
    (net (code "82") (name "unconnected-(U10-(HS1_DATA5)GPIO17-Pad27)") (class "Default")
      (node (ref "U10") (pin "27") (pinfunction "(HS1_DATA5)GPIO17_27") (pintype "bidirectional"))
    )
    (net (code "83") (name "unconnected-(U10-(VSPICS0{slash}HS1_DATA6)GPIO5-Pad34)") (class "Default")
      (node (ref "U10") (pin "34") (pinfunction "(VSPICS0/HS1_DATA6)GPIO5_34") (pintype "bidirectional"))
    )
    (net (code "84") (name "unconnected-(U10-(VSPIHD{slash}HS2_CMD)GPIO21-Pad42)") (class "Default")
      (node (ref "U10") (pin "42") (pinfunction "(VSPIHD/HS2_CMD)GPIO21_42") (pintype "bidirectional"))
    )
    (net (code "85") (name "unconnected-(U10-(VSPIWP{slash}HS2_CLK)GPIO22-Pad39)") (class "Default")
      (node (ref "U10") (pin "39") (pinfunction "(VSPIWP/HS2_CLK)GPIO22_39") (pintype "bidirectional"))
    )
    (net (code "86") (name "unconnected-(U10-SENSOR_CAPP(GPI37{slash}ADC1:1{slash}RTC1)-Pad6)") (class "Default")
      (node (ref "U10") (pin "6") (pinfunction "SENSOR_CAPP(GPI37/ADC1:1/RTC1)_6") (pintype "bidirectional"))
    )
    (net (code "87") (name "unconnected-(U10-VDET_1(GPI34{slash}ADC1:6)-Pad10)") (class "Default")
      (node (ref "U10") (pin "10") (pinfunction "VDET_1(GPI34/ADC1:6)_10") (pintype "bidirectional"))
    )
    (net (code "88") (name "unconnected-(U10-VDET_2(GPI35{slash}ADC1:7)-Pad11)") (class "Default")
      (node (ref "U10") (pin "11") (pinfunction "VDET_2(GPI35/ADC1:7)_11") (pintype "bidirectional"))
    )
  )
)
